# INS_2.net
KiCad netlist of a schematic drawn in EAGLE
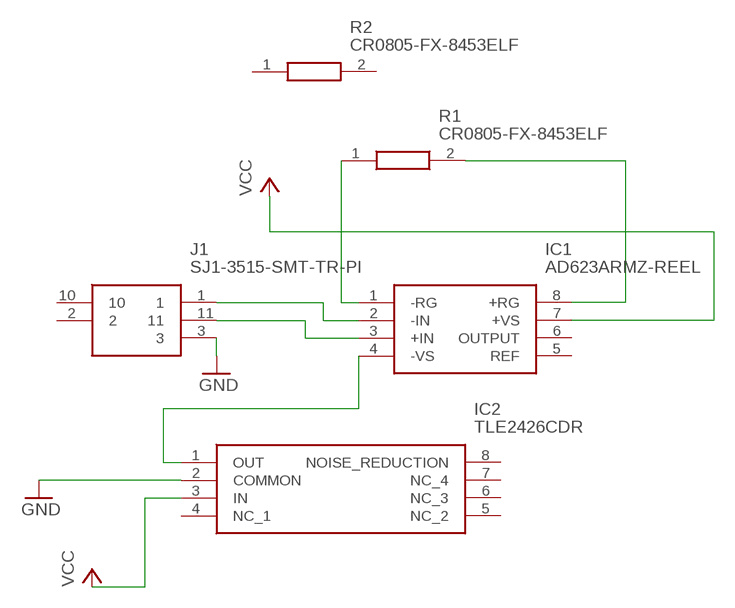
[diagram p0: schematic, sheet 1]

(export (version "E")
  (design (tool "Eeschema 10.0.6"))
  (components
    (comp (ref "IC1")
      (value "AD623ARMZ-REEL")
      (footprint "eagle-import:SOP65P490X110-8N")
      (fields (field (name "MOUSER_PART_NUMBER") "584-AD623ARMZ-R"))
      (libsource (lib "eagle-import") (part "AD623ARMZ-REEL"))
    )
    (comp (ref "IC2")
      (value "TLE2426CDR")
      (footprint "eagle-import:SOIC127P600X175-8N")
      (fields (field (name "MOUSER_PART_NUMBER") "595-TLE2426CDR"))
      (libsource (lib "eagle-import") (part "TLE2426CDR"))
    )
    (comp (ref "J1")
      (value "SJ1-3515-SMT-TR-PI")
      (footprint "eagle-import:SJ13515SMTTRPI")
      (fields (field (name "MOUSER_PART_NUMBER") "490-SJ13515SMTTRPI"))
      (libsource (lib "eagle-import") (part "SJ1-3515-SMT-TR-PI"))
    )
    (comp (ref "R1")
      (value "CR0805-FX-8453ELF")
      (footprint "eagle-import:RESC2012X60N")
      (fields (field (name "MOUSER_PART_NUMBER") "652-CR0805FX-8453ELF"))
      (libsource (lib "eagle-import") (part "CR0805-FX-8453ELF"))
    )
    (comp (ref "R2")
      (value "CR0805-FX-8453ELF")
      (footprint "eagle-import:RESC2012X60N")
      (fields (field (name "MOUSER_PART_NUMBER") "652-CR0805FX-8453ELF"))
      (libsource (lib "eagle-import") (part "CR0805-FX-8453ELF"))
    )
  )
  (nets
    (net (code "1") (name "GND") (class "Default")
      (node (ref "IC2") (pin "2") (pinfunction "COMMON_2") (pintype "bidirectional"))
      (node (ref "J1") (pin "3") (pinfunction "3_3") (pintype "bidirectional"))
    )
    (net (code "2") (name "Net-(IC1-+IN)") (class "Default")
      (node (ref "IC1") (pin "3") (pinfunction "+IN_3") (pintype "bidirectional"))
      (node (ref "J1") (pin "11") (pinfunction "11_11") (pintype "bidirectional"))
    )
    (net (code "3") (name "Net-(IC1-+RG)") (class "Default")
      (node (ref "IC1") (pin "8") (pinfunction "+RG_8") (pintype "bidirectional"))
      (node (ref "R1") (pin "2") (pinfunction "2_2") (pintype "bidirectional"))
    )
    (net (code "4") (name "Net-(IC1--IN)") (class "Default")
      (node (ref "IC1") (pin "2") (pinfunction "-IN_2") (pintype "bidirectional"))
      (node (ref "J1") (pin "1") (pinfunction "1_1") (pintype "bidirectional"))
    )
    (net (code "5") (name "Net-(IC1--RG)") (class "Default")
      (node (ref "IC1") (pin "1") (pinfunction "-RG_1") (pintype "bidirectional"))
      (node (ref "R1") (pin "1") (pinfunction "1_1") (pintype "bidirectional"))
    )
    (net (code "6") (name "Net-(IC1--VS)") (class "Default")
      (node (ref "IC1") (pin "4") (pinfunction "-VS_4") (pintype "bidirectional"))
      (node (ref "IC2") (pin "1") (pinfunction "OUT_1") (pintype "bidirectional"))
    )
    (net (code "7") (name "VCC") (class "Default")
      (node (ref "IC1") (pin "7") (pinfunction "+VS_7") (pintype "bidirectional"))
      (node (ref "IC2") (pin "3") (pinfunction "IN_3") (pintype "bidirectional"))
    )
    (net (code "8") (name "unconnected-(IC1-OUTPUT-Pad6)") (class "Default")
      (node (ref "IC1") (pin "6") (pinfunction "OUTPUT_6") (pintype "bidirectional"))
    )
    (net (code "9") (name "unconnected-(IC1-REF-Pad5)") (class "Default")
      (node (ref "IC1") (pin "5") (pinfunction "REF_5") (pintype "bidirectional"))
    )
    (net (code "10") (name "unconnected-(IC2-NC_1-Pad4)") (class "Default")
      (node (ref "IC2") (pin "4") (pinfunction "NC_1_4") (pintype "bidirectional"))
    )
    (net (code "11") (name "unconnected-(IC2-NC_2-Pad5)") (class "Default")
      (node (ref "IC2") (pin "5") (pinfunction "NC_2_5") (pintype "bidirectional"))
    )
    (net (code "12") (name "unconnected-(IC2-NC_3-Pad6)") (class "Default")
      (node (ref "IC2") (pin "6") (pinfunction "NC_3_6") (pintype "bidirectional"))
    )
    (net (code "13") (name "unconnected-(IC2-NC_4-Pad7)") (class "Default")
      (node (ref "IC2") (pin "7") (pinfunction "NC_4_7") (pintype "bidirectional"))
    )
    (net (code "14") (name "unconnected-(IC2-NOISE_REDUCTION-Pad8)") (class "Default")
      (node (ref "IC2") (pin "8") (pinfunction "NOISE_REDUCTION_8") (pintype "bidirectional"))
    )
    (net (code "15") (name "unconnected-(J1-Pad2)") (class "Default")
      (node (ref "J1") (pin "2") (pinfunction "2_2") (pintype "bidirectional"))
    )
    (net (code "16") (name "unconnected-(J1-Pad10)") (class "Default")
      (node (ref "J1") (pin "10") (pinfunction "10_10") (pintype "bidirectional"))
    )
    (net (code "17") (name "unconnected-(R2-Pad1)") (class "Default")
      (node (ref "R2") (pin "1") (pinfunction "1_1") (pintype "bidirectional"))
    )
    (net (code "18") (name "unconnected-(R2-Pad2)") (class "Default")
      (node (ref "R2") (pin "2") (pinfunction "2_2") (pintype "bidirectional"))
    )
  )
)
